# CPU.net
KiCad netlist of a schematic drawn in Altium Designer
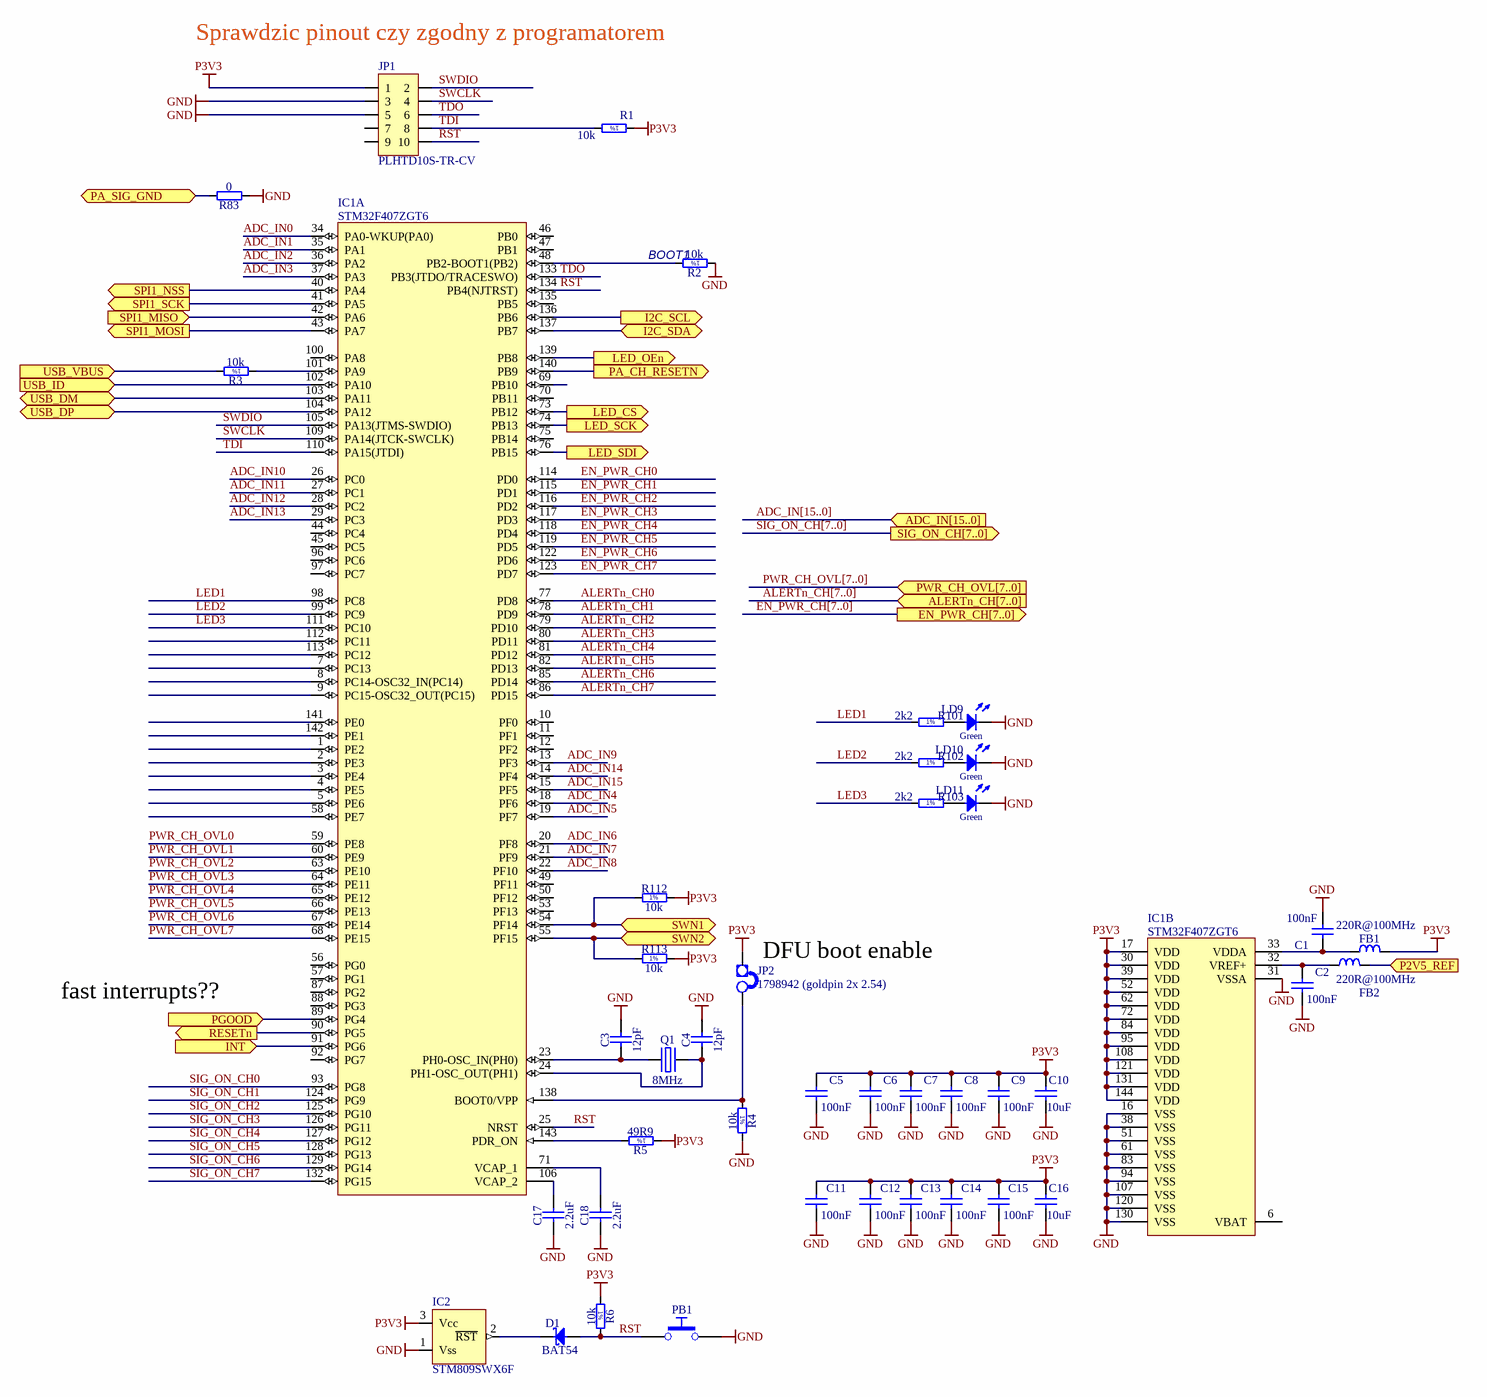
[diagram p0: CPU.SchDoc]

(export (version "E")
  (design (tool "Eeschema 10.0.6"))
  (components
    (comp (ref "C1")
      (value "100nF")
      (footprint "CAPC0603X33N")
      (description "Non-polarised capacitor")
      (fields
        (field (name "PART NUMBER") "CC0201_100NF_6.3V_10%_X5R")
        (field (name "VOLTAGE") "6.3V")
        (field (name "AUTHOR") "CERN DEM JLC")
      )
      (libsource (lib "Capacitors") (part "Capacitor - non polarized"))
    )
    (comp (ref "C2")
      (value "100nF")
      (footprint "CAPC0603X33N")
      (description "Non-polarised capacitor")
      (fields
        (field (name "PART NUMBER") "CC0201_100NF_6.3V_10%_X5R")
        (field (name "VOLTAGE") "6.3V")
        (field (name "AUTHOR") "CERN DEM JLC")
      )
      (libsource (lib "Capacitors") (part "Capacitor - non polarized"))
    )
    (comp (ref "C3")
      (value "12pF")
      (footprint "CAPC1005X55N")
      (description "Non-polarised capacitor")
      (fields
        (field (name "PART NUMBER") "CC0402_12PF_50V_5%_C0G")
        (field (name "VOLTAGE") "50V")
        (field (name "AUTHOR") "CERN DEM JLC")
      )
      (libsource (lib "Capacitors") (part "Capacitor - non polarized"))
    )
    (comp (ref "C4")
      (value "12pF")
      (footprint "CAPC1005X55N")
      (description "Non-polarised capacitor")
      (fields
        (field (name "PART NUMBER") "CC0402_12PF_50V_5%_C0G")
        (field (name "VOLTAGE") "50V")
        (field (name "AUTHOR") "CERN DEM JLC")
      )
      (libsource (lib "Capacitors") (part "Capacitor - non polarized"))
    )
    (comp (ref "C5")
      (value "100nF")
      (footprint "CAPC0603X33N")
      (description "Non-polarised capacitor")
      (fields
        (field (name "PART NUMBER") "CC0201_100NF_6.3V_10%_X5R")
        (field (name "VOLTAGE") "6.3V")
        (field (name "AUTHOR") "CERN DEM JLC")
      )
      (libsource (lib "Capacitors") (part "Capacitor - non polarized"))
    )
    (comp (ref "C6")
      (value "100nF")
      (footprint "CAPC0603X33N")
      (description "Non-polarised capacitor")
      (fields
        (field (name "PART NUMBER") "CC0201_100NF_6.3V_10%_X5R")
        (field (name "VOLTAGE") "6.3V")
        (field (name "AUTHOR") "CERN DEM JLC")
      )
      (libsource (lib "Capacitors") (part "Capacitor - non polarized"))
    )
    (comp (ref "C7")
      (value "100nF")
      (footprint "CAPC0603X33N")
      (description "Non-polarised capacitor")
      (fields
        (field (name "PART NUMBER") "CC0201_100NF_6.3V_10%_X5R")
        (field (name "VOLTAGE") "6.3V")
        (field (name "AUTHOR") "CERN DEM JLC")
      )
      (libsource (lib "Capacitors") (part "Capacitor - non polarized"))
    )
    (comp (ref "C8")
      (value "100nF")
      (footprint "CAPC0603X33N")
      (description "Non-polarised capacitor")
      (fields
        (field (name "PART NUMBER") "CC0201_100NF_6.3V_10%_X5R")
        (field (name "VOLTAGE") "6.3V")
        (field (name "AUTHOR") "CERN DEM JLC")
      )
      (libsource (lib "Capacitors") (part "Capacitor - non polarized"))
    )
    (comp (ref "C9")
      (value "100nF")
      (footprint "CAPC0603X33N")
      (description "Non-polarised capacitor")
      (fields
        (field (name "PART NUMBER") "CC0201_100NF_6.3V_10%_X5R")
        (field (name "VOLTAGE") "6.3V")
        (field (name "AUTHOR") "CERN DEM JLC")
      )
      (libsource (lib "Capacitors") (part "Capacitor - non polarized"))
    )
    (comp (ref "C10")
      (value "10uF")
      (footprint "CAPC2012X135N")
      (description "Non-polarised capacitor")
      (fields
        (field (name "PART NUMBER") "CC0805_10UF_10V_10%_X7R")
        (field (name "VOLTAGE") "10V")
        (field (name "AUTHOR") "CERN DEM JLC")
      )
      (libsource (lib "Capacitors") (part "Capacitor - non polarized"))
    )
    (comp (ref "C11")
      (value "100nF")
      (footprint "CAPC0603X33N")
      (description "Non-polarised capacitor")
      (fields
        (field (name "PART NUMBER") "CC0201_100NF_6.3V_10%_X5R")
        (field (name "VOLTAGE") "6.3V")
        (field (name "AUTHOR") "CERN DEM JLC")
      )
      (libsource (lib "Capacitors") (part "Capacitor - non polarized"))
    )
    (comp (ref "C12")
      (value "100nF")
      (footprint "CAPC0603X33N")
      (description "Non-polarised capacitor")
      (fields
        (field (name "PART NUMBER") "CC0201_100NF_6.3V_10%_X5R")
        (field (name "VOLTAGE") "6.3V")
        (field (name "AUTHOR") "CERN DEM JLC")
      )
      (libsource (lib "Capacitors") (part "Capacitor - non polarized"))
    )
    (comp (ref "C13")
      (value "100nF")
      (footprint "CAPC0603X33N")
      (description "Non-polarised capacitor")
      (fields
        (field (name "PART NUMBER") "CC0201_100NF_6.3V_10%_X5R")
        (field (name "VOLTAGE") "6.3V")
        (field (name "AUTHOR") "CERN DEM JLC")
      )
      (libsource (lib "Capacitors") (part "Capacitor - non polarized"))
    )
    (comp (ref "C14")
      (value "100nF")
      (footprint "CAPC0603X33N")
      (description "Non-polarised capacitor")
      (fields
        (field (name "PART NUMBER") "CC0201_100NF_6.3V_10%_X5R")
        (field (name "VOLTAGE") "6.3V")
        (field (name "AUTHOR") "CERN DEM JLC")
      )
      (libsource (lib "Capacitors") (part "Capacitor - non polarized"))
    )
    (comp (ref "C15")
      (value "100nF")
      (footprint "CAPC0603X33N")
      (description "Non-polarised capacitor")
      (fields
        (field (name "PART NUMBER") "CC0201_100NF_6.3V_10%_X5R")
        (field (name "VOLTAGE") "6.3V")
        (field (name "AUTHOR") "CERN DEM JLC")
      )
      (libsource (lib "Capacitors") (part "Capacitor - non polarized"))
    )
    (comp (ref "C16")
      (value "10uF")
      (footprint "CAPC2012X135N")
      (description "Non-polarised capacitor")
      (fields
        (field (name "PART NUMBER") "CC0805_10UF_10V_10%_X7R")
        (field (name "VOLTAGE") "10V")
        (field (name "AUTHOR") "CERN DEM JLC")
      )
      (libsource (lib "Capacitors") (part "Capacitor - non polarized"))
    )
    (comp (ref "C17")
      (value "2.2uF")
      (footprint "CAPC1608X90N")
      (description "Non-polarised capacitor")
      (fields
        (field (name "PART NUMBER") "CC0603_2.2UF_10V_20%_X7R")
        (field (name "VOLTAGE") "10V")
        (field (name "AUTHOR") "CERN DEM JLC")
      )
      (libsource (lib "Capacitors") (part "Capacitor - non polarized"))
    )
    (comp (ref "C18")
      (value "2.2uF")
      (footprint "CAPC1608X90N")
      (description "Non-polarised capacitor")
      (fields
        (field (name "PART NUMBER") "CC0603_2.2UF_10V_20%_X7R")
        (field (name "VOLTAGE") "10V")
        (field (name "AUTHOR") "CERN DEM JLC")
      )
      (libsource (lib "Capacitors") (part "Capacitor - non polarized"))
    )
    (comp (ref "D1")
      (value "BAT54")
      (footprint "SOT95P240X130-3N")
      (description "Diode Schottky  Anode Pin 1 Cathode Pin 3 (Pas de pin 2)")
      (fields
        (field (name "VOLTAGE") "30V")
        (field (name "POWER") "200mA")
        (field (name "AUTHOR") "CERN DEM JLC")
      )
      (libsource (lib "ICs And Semiconductors") (part "Diode Schottky A1C3"))
    )
    (comp (ref "FB1")
      (value "220R@100MHz")
      (footprint "INDC2012X105N")
      (description "Inductor")
      (fields
        (field (name "PART NUMBER") "IND0805_MURATA_BLM21PG221SN1D")
        (field (name "POWER") "2A")
        (field (name "AUTHOR") "CERN DEM JLC")
      )
      (libsource (lib "Inductors & Transformers") (part "Inductor"))
    )
    (comp (ref "FB2")
      (value "220R@100MHz")
      (footprint "INDC2012X105N")
      (description "Inductor")
      (fields
        (field (name "PART NUMBER") "IND0805_MURATA_BLM21PG221SN1D")
        (field (name "POWER") "2A")
        (field (name "AUTHOR") "CERN DEM JLC")
      )
      (libsource (lib "Inductors & Transformers") (part "Inductor"))
    )
    (comp (ref "IC1")
      (value "STM32F407ZGT6")
      (footprint "QFP50P2200X2200X160-144N")
      (fields (field (name "MANUFACTURER") "ST MICROELECTRONICS") (field (name "AUTHOR") "CERN DEM MR"))
      (libsource (lib "ICs And Semiconductors") (part "STM32F407ZGT6"))
    )
    (comp (ref "IC2")
      (value "STM809SWX6F")
      (footprint "SOT-23")
      (description "2.93V  Reset circuit")
      (libsource (lib "LIBRARY_SCH") (part "VMON_STM809"))
    )
    (comp (ref "JP1")
      (value "PLHTD10S-TR-CV")
      (footprint "PLHTD10S-TR-CV")
      (description "1.27 mm dual row goldpin (Maritex)")
      (libsource (lib "LIBRARY_SCH") (part "CON_2x5 1.27 SMT Male"))
    )
    (comp (ref "JP2")
      (value "1798942 (goldpin 2x 2.54)")
      (footprint "jump")
      (description "Jumper")
      (libsource (lib "LIBRARY_SCH") (part "JUMPER"))
    )
    (comp (ref "LD9")
      (value "Green")
      (footprint "LED_OSRAM_LGL29K")
      (description "LED Green 1C 2A")
      (fields
        (field (name "PART NUMBER") "LED_OSRAM_LG L29K-G2J1-24-Z")
        (field (name "MANUFACTURER") "OSRAM")
        (field (name "AUTHOR") "CERN DEM JLC")
      )
      (libsource (lib "ICs And Semiconductors") (part "LED Green 1C 2A"))
    )
    (comp (ref "LD10")
      (value "Green")
      (footprint "LED_OSRAM_LGL29K")
      (description "LED Green 1C 2A")
      (fields
        (field (name "PART NUMBER") "LED_OSRAM_LG L29K-G2J1-24-Z")
        (field (name "MANUFACTURER") "OSRAM")
        (field (name "AUTHOR") "CERN DEM JLC")
      )
      (libsource (lib "ICs And Semiconductors") (part "LED Green 1C 2A"))
    )
    (comp (ref "LD11")
      (value "Green")
      (footprint "LED_OSRAM_LGL29K")
      (description "LED Green 1C 2A")
      (fields
        (field (name "PART NUMBER") "LED_OSRAM_LG L29K-G2J1-24-Z")
        (field (name "MANUFACTURER") "OSRAM")
        (field (name "AUTHOR") "CERN DEM JLC")
      )
      (libsource (lib "ICs And Semiconductors") (part "LED Green 1C 2A"))
    )
    (comp (ref "PB1")
      (value "Push Button")
      (footprint "PB_TYCO_FSMSM")
      (description "Push-Button Switch SPDT")
      (fields
        (field (name "PART NUMBER") "PB_TYCO_FSMSM")
        (field (name "MANUFACTURER") "TYCO ELECTRONICS")
        (field (name "AUTHOR") "CERN DEM JLC")
      )
      (libsource (lib "Eletro-mechanical") (part "PB SPST 1NO-2NO"))
    )
    (comp (ref "Q1")
      (value "8MHz")
      (footprint "XTAL_TXC_7A")
      (description "Quartz Crystal")
      (fields
        (field (name "PART NUMBER") "XTAL_8MHZ_TXC_7A-8.000MAAE-T")
        (field (name "MANUFACTURER") "TXC CORPORATION")
        (field (name "AUTHOR") "CERN DEM JLC")
      )
      (libsource (lib "ICs And Semiconductors") (part "Quartz Crystal"))
    )
    (comp (ref "R1")
      (value "10k")
      (footprint "RESC1005X40N")
      (description "Resistor - 1%")
      (fields
        (field (name "PART NUMBER") "R0402_10K_1%_0.0625W_100PPM")
        (field (name "POWER") "0.0625W")
        (field (name "AUTHOR") "CERN DEM JLC")
      )
      (libsource (lib "Resistors") (part "Resistor - 1%"))
    )
    (comp (ref "R2")
      (value "10k")
      (footprint "RESC1005X40N")
      (description "Resistor - 1%")
      (fields
        (field (name "PART NUMBER") "R0402_10K_1%_0.0625W_100PPM")
        (field (name "POWER") "0.0625W")
        (field (name "AUTHOR") "CERN DEM JLC")
      )
      (libsource (lib "Resistors") (part "Resistor - 1%"))
    )
    (comp (ref "R3")
      (value "10k")
      (footprint "RESC1005X40N")
      (description "Resistor - 1%")
      (fields
        (field (name "PART NUMBER") "R0402_10K_1%_0.0625W_100PPM")
        (field (name "POWER") "0.0625W")
        (field (name "AUTHOR") "CERN DEM JLC")
      )
      (libsource (lib "Resistors") (part "Resistor - 1%"))
    )
    (comp (ref "R4")
      (value "10k")
      (footprint "RESC1005X40N")
      (description "Resistor - 1%")
      (fields
        (field (name "PART NUMBER") "R0402_10K_1%_0.0625W_100PPM")
        (field (name "POWER") "0.0625W")
        (field (name "AUTHOR") "CERN DEM JLC")
      )
      (libsource (lib "Resistors") (part "Resistor - 1%"))
    )
    (comp (ref "R5")
      (value "49R9")
      (footprint "RESC1005X40N")
      (description "Resistor - 1%")
      (fields
        (field (name "PART NUMBER") "R0402_49R9_1%_0.0625W_100PPM")
        (field (name "POWER") "0.0625W")
        (field (name "AUTHOR") "CERN DEM JLC")
      )
      (libsource (lib "Resistors") (part "Resistor - 1%"))
    )
    (comp (ref "R6")
      (value "10k")
      (footprint "RESC1005X40N")
      (description "Resistor - 1%")
      (fields
        (field (name "PART NUMBER") "R0402_10K_1%_0.0625W_100PPM")
        (field (name "POWER") "0.0625W")
        (field (name "AUTHOR") "CERN DEM JLC")
      )
      (libsource (lib "Resistors") (part "Resistor - 1%"))
    )
    (comp (ref "R83")
      (value "0")
      (footprint "RESC1005X40N")
      (description "Resistor")
      (fields
        (field (name "PART NUMBER") "R0402_0R_JUMPER")
        (field (name "MANUFACTURER") "GENERIC")
        (field (name "AUTHOR") "CERN DEM JLC")
      )
      (libsource (lib "Resistors") (part "Resistor"))
    )
    (comp (ref "R101")
      (value "2k2")
      (footprint "RESC1005X40N")
      (description "Resistor - 1%")
      (fields
        (field (name "PART NUMBER") "R0402_2K2_1%_0.0625W_100PPM")
        (field (name "POWER") "0.0625W")
        (field (name "AUTHOR") "CERN DEM JLC")
      )
      (libsource (lib "Resistors") (part "Resistor - 1%"))
    )
    (comp (ref "R102")
      (value "2k2")
      (footprint "RESC1005X40N")
      (description "Resistor - 1%")
      (fields
        (field (name "PART NUMBER") "R0402_2K2_1%_0.0625W_100PPM")
        (field (name "POWER") "0.0625W")
        (field (name "AUTHOR") "CERN DEM JLC")
      )
      (libsource (lib "Resistors") (part "Resistor - 1%"))
    )
    (comp (ref "R103")
      (value "2k2")
      (footprint "RESC1005X40N")
      (description "Resistor - 1%")
      (fields
        (field (name "PART NUMBER") "R0402_2K2_1%_0.0625W_100PPM")
        (field (name "POWER") "0.0625W")
        (field (name "AUTHOR") "CERN DEM JLC")
      )
      (libsource (lib "Resistors") (part "Resistor - 1%"))
    )
    (comp (ref "R112")
      (value "10k")
      (footprint "RESC1005X40N")
      (description "Resistor - 1%")
      (fields
        (field (name "PART NUMBER") "R0402_10K_1%_0.0625W_100PPM")
        (field (name "POWER") "0.0625W")
        (field (name "AUTHOR") "CERN DEM JLC")
      )
      (libsource (lib "Resistors") (part "Resistor - 1%"))
    )
    (comp (ref "R113")
      (value "10k")
      (footprint "RESC1005X40N")
      (description "Resistor - 1%")
      (fields
        (field (name "PART NUMBER") "R0402_10K_1%_0.0625W_100PPM")
        (field (name "POWER") "0.0625W")
        (field (name "AUTHOR") "CERN DEM JLC")
      )
      (libsource (lib "Resistors") (part "Resistor - 1%"))
    )
  )
  (nets
    (net (code "1") (name "/ADC_IN0") (class "Default")
      (node (ref "IC1") (pin "34") (pinfunction "PA0-WKUP(PA0)_34") (pintype "bidirectional"))
    )
    (net (code "2") (name "/ADC_IN1") (class "Default")
      (node (ref "IC1") (pin "35") (pinfunction "PA1_35") (pintype "bidirectional"))
    )
    (net (code "3") (name "/ADC_IN2") (class "Default")
      (node (ref "IC1") (pin "36") (pinfunction "PA2_36") (pintype "bidirectional"))
    )
    (net (code "4") (name "/ADC_IN3") (class "Default")
      (node (ref "IC1") (pin "37") (pinfunction "PA3_37") (pintype "bidirectional"))
    )
    (net (code "5") (name "/ADC_IN4") (class "Default")
      (node (ref "IC1") (pin "18") (pinfunction "PF6_18") (pintype "bidirectional"))
    )
    (net (code "6") (name "/ADC_IN5") (class "Default")
      (node (ref "IC1") (pin "19") (pinfunction "PF7_19") (pintype "bidirectional"))
    )
    (net (code "7") (name "/ADC_IN6") (class "Default")
      (node (ref "IC1") (pin "20") (pinfunction "PF8_20") (pintype "bidirectional"))
    )
    (net (code "8") (name "/ADC_IN7") (class "Default")
      (node (ref "IC1") (pin "21") (pinfunction "PF9_21") (pintype "bidirectional"))
    )
    (net (code "9") (name "/ADC_IN8") (class "Default")
      (node (ref "IC1") (pin "22") (pinfunction "PF10_22") (pintype "bidirectional"))
    )
    (net (code "10") (name "/ADC_IN9") (class "Default")
      (node (ref "IC1") (pin "13") (pinfunction "PF3_13") (pintype "bidirectional"))
    )
    (net (code "11") (name "/ADC_IN10") (class "Default")
      (node (ref "IC1") (pin "26") (pinfunction "PC0_26") (pintype "bidirectional"))
    )
    (net (code "12") (name "/ADC_IN11") (class "Default")
      (node (ref "IC1") (pin "27") (pinfunction "PC1_27") (pintype "bidirectional"))
    )
    (net (code "13") (name "/ADC_IN12") (class "Default")
      (node (ref "IC1") (pin "28") (pinfunction "PC2_28") (pintype "bidirectional"))
    )
    (net (code "14") (name "/ADC_IN13") (class "Default")
      (node (ref "IC1") (pin "29") (pinfunction "PC3_29") (pintype "bidirectional"))
    )
    (net (code "15") (name "/ADC_IN14") (class "Default")
      (node (ref "IC1") (pin "14") (pinfunction "PF4_14") (pintype "bidirectional"))
    )
    (net (code "16") (name "/ADC_IN15") (class "Default")
      (node (ref "IC1") (pin "15") (pinfunction "PF5_15") (pintype "bidirectional"))
    )
    (net (code "18") (name "/ALERTn_CH0") (class "Default")
      (node (ref "IC1") (pin "77") (pinfunction "PD8_77") (pintype "bidirectional"))
    )
    (net (code "19") (name "/ALERTn_CH1") (class "Default")
      (node (ref "IC1") (pin "78") (pinfunction "PD9_78") (pintype "bidirectional"))
    )
    (net (code "20") (name "/ALERTn_CH2") (class "Default")
      (node (ref "IC1") (pin "79") (pinfunction "PD10_79") (pintype "bidirectional"))
    )
    (net (code "21") (name "/ALERTn_CH3") (class "Default")
      (node (ref "IC1") (pin "80") (pinfunction "PD11_80") (pintype "bidirectional"))
    )
    (net (code "22") (name "/ALERTn_CH4") (class "Default")
      (node (ref "IC1") (pin "81") (pinfunction "PD12_81") (pintype "bidirectional"))
    )
    (net (code "23") (name "/ALERTn_CH5") (class "Default")
      (node (ref "IC1") (pin "82") (pinfunction "PD13_82") (pintype "bidirectional"))
    )
    (net (code "24") (name "/ALERTn_CH6") (class "Default")
      (node (ref "IC1") (pin "85") (pinfunction "PD14_85") (pintype "bidirectional"))
    )
    (net (code "25") (name "/ALERTn_CH7") (class "Default")
      (node (ref "IC1") (pin "86") (pinfunction "PD15_86") (pintype "bidirectional"))
    )
    (net (code "27") (name "/EN_PWR_CH0") (class "Default")
      (node (ref "IC1") (pin "114") (pinfunction "PD0_114") (pintype "bidirectional"))
    )
    (net (code "28") (name "/EN_PWR_CH1") (class "Default")
      (node (ref "IC1") (pin "115") (pinfunction "PD1_115") (pintype "bidirectional"))
    )
    (net (code "29") (name "/EN_PWR_CH2") (class "Default")
      (node (ref "IC1") (pin "116") (pinfunction "PD2_116") (pintype "bidirectional"))
    )
    (net (code "30") (name "/EN_PWR_CH3") (class "Default")
      (node (ref "IC1") (pin "117") (pinfunction "PD3_117") (pintype "bidirectional"))
    )
    (net (code "31") (name "/EN_PWR_CH4") (class "Default")
      (node (ref "IC1") (pin "118") (pinfunction "PD4_118") (pintype "bidirectional"))
    )
    (net (code "32") (name "/EN_PWR_CH5") (class "Default")
      (node (ref "IC1") (pin "119") (pinfunction "PD5_119") (pintype "bidirectional"))
    )
    (net (code "33") (name "/EN_PWR_CH6") (class "Default")
      (node (ref "IC1") (pin "122") (pinfunction "PD6_122") (pintype "bidirectional"))
    )
    (net (code "34") (name "/EN_PWR_CH7") (class "Default")
      (node (ref "IC1") (pin "123") (pinfunction "PD7_123") (pintype "bidirectional"))
    )
    (net (code "36") (name "/I2C_SCL") (class "Default")
      (node (ref "IC1") (pin "136") (pinfunction "PB6_136") (pintype "bidirectional"))
    )
    (net (code "37") (name "/I2C_SDA") (class "Default")
      (node (ref "IC1") (pin "137") (pinfunction "PB7_137") (pintype "bidirectional"))
    )
    (net (code "38") (name "/INT") (class "Default")
      (node (ref "IC1") (pin "91") (pinfunction "PG6_91") (pintype "bidirectional"))
    )
    (net (code "39") (name "/LED1") (class "Default")
      (node (ref "IC1") (pin "98") (pinfunction "PC8_98") (pintype "bidirectional"))
      (node (ref "R101") (pin "1") (pinfunction "1_1") (pintype "passive"))
    )
    (net (code "40") (name "/LED2") (class "Default")
      (node (ref "IC1") (pin "99") (pinfunction "PC9_99") (pintype "bidirectional"))
      (node (ref "R102") (pin "1") (pinfunction "1_1") (pintype "passive"))
    )
    (net (code "41") (name "/LED3") (class "Default")
      (node (ref "IC1") (pin "111") (pinfunction "PC10_111") (pintype "bidirectional"))
      (node (ref "R103") (pin "1") (pinfunction "1_1") (pintype "passive"))
    )
    (net (code "42") (name "/LED_CS") (class "Default")
      (node (ref "IC1") (pin "73") (pinfunction "PB12_73") (pintype "bidirectional"))
    )
    (net (code "43") (name "/LED_OEn") (class "Default")
      (node (ref "IC1") (pin "139") (pinfunction "PB8_139") (pintype "bidirectional"))
    )
    (net (code "44") (name "/LED_SCK") (class "Default")
      (node (ref "IC1") (pin "74") (pinfunction "PB13_74") (pintype "bidirectional"))
    )
    (net (code "45") (name "/LED_SDI") (class "Default")
      (node (ref "IC1") (pin "76") (pinfunction "PB15_76") (pintype "bidirectional"))
    )
    (net (code "46") (name "/P2V5_REF") (class "Default")
      (node (ref "FB2") (pin "2") (pinfunction "2_2") (pintype "passive"))
    )
    (net (code "47") (name "/PA_CH_RESETN") (class "Default")
      (node (ref "IC1") (pin "140") (pinfunction "PB9_140") (pintype "bidirectional"))
    )
    (net (code "48") (name "/PA_SIG_GND") (class "Default")
      (node (ref "R83") (pin "2") (pinfunction "2_2") (pintype "passive"))
    )
    (net (code "49") (name "/PGOOD") (class "Default")
      (node (ref "IC1") (pin "89") (pinfunction "PG4_89") (pintype "bidirectional"))
    )
    (net (code "50") (name "/PWR_CH_OVL0") (class "Default")
      (node (ref "IC1") (pin "59") (pinfunction "PE8_59") (pintype "bidirectional"))
    )
    (net (code "51") (name "/PWR_CH_OVL1") (class "Default")
      (node (ref "IC1") (pin "60") (pinfunction "PE9_60") (pintype "bidirectional"))
    )
    (net (code "52") (name "/PWR_CH_OVL2") (class "Default")
      (node (ref "IC1") (pin "63") (pinfunction "PE10_63") (pintype "bidirectional"))
    )
    (net (code "53") (name "/PWR_CH_OVL3") (class "Default")
      (node (ref "IC1") (pin "64") (pinfunction "PE11_64") (pintype "bidirectional"))
    )
    (net (code "54") (name "/PWR_CH_OVL4") (class "Default")
      (node (ref "IC1") (pin "65") (pinfunction "PE12_65") (pintype "bidirectional"))
    )
    (net (code "55") (name "/PWR_CH_OVL5") (class "Default")
      (node (ref "IC1") (pin "66") (pinfunction "PE13_66") (pintype "bidirectional"))
    )
    (net (code "56") (name "/PWR_CH_OVL6") (class "Default")
      (node (ref "IC1") (pin "67") (pinfunction "PE14_67") (pintype "bidirectional"))
    )
    (net (code "57") (name "/PWR_CH_OVL7") (class "Default")
      (node (ref "IC1") (pin "68") (pinfunction "PE15_68") (pintype "bidirectional"))
    )
    (net (code "59") (name "/RESETn") (class "Default")
      (node (ref "IC1") (pin "90") (pinfunction "PG5_90") (pintype "bidirectional"))
    )
    (net (code "60") (name "/RST") (class "Default")
      (node (ref "D1") (pin "1") (pinfunction "A_1") (pintype "passive"))
      (node (ref "IC1") (pin "134") (pinfunction "PB4(NJTRST)_134") (pintype "bidirectional"))
      (node (ref "IC1") (pin "25") (pinfunction "NRST_25") (pintype "bidirectional"))
      (node (ref "JP1") (pin "10") (pinfunction "10_10") (pintype "passive"))
      (node (ref "PB1") (pin "1") (pinfunction "1_1") (pintype "passive"))
      (node (ref "R6") (pin "2") (pinfunction "2_2") (pintype "passive"))
    )
    (net (code "61") (name "/SIG_ON_CH0") (class "Default")
      (node (ref "IC1") (pin "93") (pinfunction "PG8_93") (pintype "bidirectional"))
    )
    (net (code "62") (name "/SIG_ON_CH1") (class "Default")
      (node (ref "IC1") (pin "124") (pinfunction "PG9_124") (pintype "bidirectional"))
    )
    (net (code "63") (name "/SIG_ON_CH2") (class "Default")
      (node (ref "IC1") (pin "125") (pinfunction "PG10_125") (pintype "bidirectional"))
    )
    (net (code "64") (name "/SIG_ON_CH3") (class "Default")
      (node (ref "IC1") (pin "126") (pinfunction "PG11_126") (pintype "bidirectional"))
    )
    (net (code "65") (name "/SIG_ON_CH4") (class "Default")
      (node (ref "IC1") (pin "127") (pinfunction "PG12_127") (pintype "bidirectional"))
    )
    (net (code "66") (name "/SIG_ON_CH5") (class "Default")
      (node (ref "IC1") (pin "128") (pinfunction "PG13_128") (pintype "bidirectional"))
    )
    (net (code "67") (name "/SIG_ON_CH6") (class "Default")
      (node (ref "IC1") (pin "129") (pinfunction "PG14_129") (pintype "bidirectional"))
    )
    (net (code "68") (name "/SIG_ON_CH7") (class "Default")
      (node (ref "IC1") (pin "132") (pinfunction "PG15_132") (pintype "bidirectional"))
    )
    (net (code "70") (name "/SPI1_MISO") (class "Default")
      (node (ref "IC1") (pin "42") (pinfunction "PA6_42") (pintype "bidirectional"))
    )
    (net (code "71") (name "/SPI1_MOSI") (class "Default")
      (node (ref "IC1") (pin "43") (pinfunction "PA7_43") (pintype "bidirectional"))
    )
    (net (code "72") (name "/SPI1_NSS") (class "Default")
      (node (ref "IC1") (pin "40") (pinfunction "PA4_40") (pintype "bidirectional"))
    )
    (net (code "73") (name "/SPI1_SCK") (class "Default")
      (node (ref "IC1") (pin "41") (pinfunction "PA5_41") (pintype "bidirectional"))
    )
    (net (code "74") (name "/SWCLK") (class "Default")
      (node (ref "IC1") (pin "109") (pinfunction "PA14(JTCK-SWCLK)_109") (pintype "bidirectional"))
      (node (ref "JP1") (pin "4") (pinfunction "4_4") (pintype "passive"))
    )
    (net (code "75") (name "/SWDIO") (class "Default")
      (node (ref "IC1") (pin "105") (pinfunction "PA13(JTMS-SWDIO)_105") (pintype "bidirectional"))
      (node (ref "JP1") (pin "2") (pinfunction "2_2") (pintype "passive"))
    )
    (net (code "76") (name "/SWN1") (class "Default")
      (node (ref "IC1") (pin "54") (pinfunction "PF14_54") (pintype "bidirectional"))
      (node (ref "R112") (pin "1") (pinfunction "1_1") (pintype "passive"))
    )
    (net (code "77") (name "/SWN2") (class "Default")
      (node (ref "IC1") (pin "55") (pinfunction "PF15_55") (pintype "bidirectional"))
      (node (ref "R113") (pin "1") (pinfunction "1_1") (pintype "passive"))
    )
    (net (code "78") (name "/TDI") (class "Default")
      (node (ref "IC1") (pin "110") (pinfunction "PA15(JTDI)_110") (pintype "bidirectional"))
      (node (ref "JP1") (pin "8") (pinfunction "8_8") (pintype "passive"))
      (node (ref "R1") (pin "2") (pinfunction "2_2") (pintype "passive"))
    )
    (net (code "79") (name "/TDO") (class "Default")
      (node (ref "IC1") (pin "133") (pinfunction "PB3(JTDO/TRACESWO)_133") (pintype "bidirectional"))
      (node (ref "JP1") (pin "6") (pinfunction "6_6") (pintype "passive"))
    )
    (net (code "80") (name "/USB_DM") (class "Default")
      (node (ref "IC1") (pin "103") (pinfunction "PA11_103") (pintype "bidirectional"))
    )
    (net (code "81") (name "/USB_DP") (class "Default")
      (node (ref "IC1") (pin "104") (pinfunction "PA12_104") (pintype "bidirectional"))
    )
    (net (code "82") (name "/USB_ID") (class "Default")
      (node (ref "IC1") (pin "102") (pinfunction "PA10_102") (pintype "bidirectional"))
    )
    (net (code "83") (name "/USB_VBUS") (class "Default")
      (node (ref "R3") (pin "2") (pinfunction "2_2") (pintype "passive"))
    )
    (net (code "84") (name "GND") (class "Default")
      (node (ref "C1") (pin "2") (pinfunction "2_2") (pintype "passive"))
      (node (ref "C10") (pin "2") (pinfunction "2_2") (pintype "passive"))
      (node (ref "C11") (pin "2") (pinfunction "2_2") (pintype "passive"))
      (node (ref "C12") (pin "2") (pinfunction "2_2") (pintype "passive"))
      (node (ref "C13") (pin "2") (pinfunction "2_2") (pintype "passive"))
      (node (ref "C14") (pin "2") (pinfunction "2_2") (pintype "passive"))
      (node (ref "C15") (pin "2") (pinfunction "2_2") (pintype "passive"))
      (node (ref "C16") (pin "2") (pinfunction "2_2") (pintype "passive"))
      (node (ref "C17") (pin "1") (pinfunction "1_1") (pintype "passive"))
      (node (ref "C18") (pin "1") (pinfunction "1_1") (pintype "passive"))
      (node (ref "C2") (pin "2") (pinfunction "2_2") (pintype "passive"))
      (node (ref "C3") (pin "2") (pinfunction "2_2") (pintype "passive"))
      (node (ref "C4") (pin "2") (pinfunction "2_2") (pintype "passive"))
      (node (ref "C5") (pin "2") (pinfunction "2_2") (pintype "passive"))
      (node (ref "C6") (pin "2") (pinfunction "2_2") (pintype "passive"))
      (node (ref "C7") (pin "2") (pinfunction "2_2") (pintype "passive"))
      (node (ref "C8") (pin "2") (pinfunction "2_2") (pintype "passive"))
      (node (ref "C9") (pin "2") (pinfunction "2_2") (pintype "passive"))
      (node (ref "IC1") (pin "107") (pinfunction "VSS_107") (pintype "power_in"))
      (node (ref "IC1") (pin "120") (pinfunction "VSS_120") (pintype "power_in"))
      (node (ref "IC1") (pin "130") (pinfunction "VSS_130") (pintype "power_in"))
      (node (ref "IC1") (pin "16") (pinfunction "VSS_16") (pintype "power_in"))
      (node (ref "IC1") (pin "31") (pinfunction "VSSA_31") (pintype "power_in"))
      (node (ref "IC1") (pin "38") (pinfunction "VSS_38") (pintype "power_in"))
      (node (ref "IC1") (pin "51") (pinfunction "VSS_51") (pintype "power_in"))
      (node (ref "IC1") (pin "61") (pinfunction "VSS_61") (pintype "power_in"))
      (node (ref "IC1") (pin "83") (pinfunction "VSS_83") (pintype "power_in"))
      (node (ref "IC1") (pin "94") (pinfunction "VSS_94") (pintype "power_in"))
      (node (ref "IC2") (pin "1") (pinfunction "Vss_1") (pintype "power_in"))
      (node (ref "JP1") (pin "3") (pinfunction "3_3") (pintype "passive"))
      (node (ref "JP1") (pin "5") (pinfunction "5_5") (pintype "passive"))
      (node (ref "LD10") (pin "1") (pinfunction "C_1") (pintype "passive"))
      (node (ref "LD11") (pin "1") (pinfunction "C_1") (pintype "passive"))
      (node (ref "LD9") (pin "1") (pinfunction "C_1") (pintype "passive"))
      (node (ref "PB1") (pin "2") (pinfunction "2_2") (pintype "passive"))
      (node (ref "R2") (pin "1") (pinfunction "1_1") (pintype "passive"))
      (node (ref "R4") (pin "2") (pinfunction "2_2") (pintype "passive"))
      (node (ref "R83") (pin "1") (pinfunction "1_1") (pintype "passive"))
    )
    (net (code "85") (name "Net-(D1-C)") (class "Default")
      (node (ref "D1") (pin "3") (pinfunction "C_3") (pintype "passive"))
      (node (ref "IC2") (pin "2") (pinfunction "~{RST}_2") (pintype "output"))
    )
    (net (code "86") (name "Net-(IC1A-BOOT0{slash}VPP)") (class "Default")
      (node (ref "IC1") (pin "138") (pinfunction "BOOT0/VPP_138") (pintype "input"))
      (node (ref "JP2") (pin "2") (pinfunction "E2_2") (pintype "passive"))
      (node (ref "R4") (pin "1") (pinfunction "1_1") (pintype "passive"))
    )
    (net (code "87") (name "Net-(IC1A-PA9)") (class "Default")
      (node (ref "IC1") (pin "101") (pinfunction "PA9_101") (pintype "bidirectional"))
      (node (ref "R3") (pin "1") (pinfunction "1_1") (pintype "passive"))
    )
    (net (code "88") (name "Net-(IC1A-PB2-BOOT1(PB2))") (class "Default")
      (node (ref "IC1") (pin "48") (pinfunction "PB2-BOOT1(PB2)_48") (pintype "bidirectional"))
      (node (ref "R2") (pin "2") (pinfunction "2_2") (pintype "passive"))
    )
    (net (code "89") (name "Net-(IC1A-PDR_ON)") (class "Default")
      (node (ref "IC1") (pin "143") (pinfunction "PDR_ON_143") (pintype "input"))
      (node (ref "R5") (pin "2") (pinfunction "2_2") (pintype "passive"))
    )
    (net (code "90") (name "Net-(IC1A-PH0-OSC_IN(PH0))") (class "Default")
      (node (ref "C3") (pin "1") (pinfunction "1_1") (pintype "passive"))
      (node (ref "IC1") (pin "23") (pinfunction "PH0-OSC_IN(PH0)_23") (pintype "bidirectional"))
      (node (ref "Q1") (pin "1") (pinfunction "OSC1_1") (pintype "passive"))
    )
    (net (code "91") (name "Net-(IC1A-PH1-OSC_OUT(PH1))") (class "Default")
      (node (ref "C4") (pin "1") (pinfunction "1_1") (pintype "passive"))
      (node (ref "IC1") (pin "24") (pinfunction "PH1-OSC_OUT(PH1)_24") (pintype "bidirectional"))
      (node (ref "Q1") (pin "2") (pinfunction "OSC2_2") (pintype "passive"))
    )
    (net (code "92") (name "Net-(IC1A-VCAP_1)") (class "Default")
      (node (ref "C18") (pin "2") (pinfunction "2_2") (pintype "passive"))
      (node (ref "IC1") (pin "71") (pinfunction "VCAP_1_71") (pintype "power_in"))
    )
    (net (code "93") (name "Net-(IC1A-VCAP_2)") (class "Default")
      (node (ref "C17") (pin "2") (pinfunction "2_2") (pintype "passive"))
      (node (ref "IC1") (pin "106") (pinfunction "VCAP_2_106") (pintype "power_in"))
    )
    (net (code "94") (name "Net-(IC1B-VDDA)") (class "Default")
      (node (ref "C1") (pin "1") (pinfunction "1_1") (pintype "passive"))
      (node (ref "FB1") (pin "1") (pinfunction "1_1") (pintype "passive"))
      (node (ref "IC1") (pin "33") (pinfunction "VDDA_33") (pintype "power_in"))
    )
    (net (code "95") (name "Net-(IC1B-VREF+)") (class "Default")
      (node (ref "C2") (pin "1") (pinfunction "1_1") (pintype "passive"))
      (node (ref "FB2") (pin "1") (pinfunction "1_1") (pintype "passive"))
      (node (ref "IC1") (pin "32") (pinfunction "VREF+_32") (pintype "power_in"))
    )
    (net (code "96") (name "Net-(LD9-A)") (class "Default")
      (node (ref "LD9") (pin "2") (pinfunction "A_2") (pintype "passive"))
      (node (ref "R101") (pin "2") (pinfunction "2_2") (pintype "passive"))
    )
    (net (code "97") (name "Net-(LD10-A)") (class "Default")
      (node (ref "LD10") (pin "2") (pinfunction "A_2") (pintype "passive"))
      (node (ref "R102") (pin "2") (pinfunction "2_2") (pintype "passive"))
    )
    (net (code "98") (name "Net-(LD11-A)") (class "Default")
      (node (ref "LD11") (pin "2") (pinfunction "A_2") (pintype "passive"))
      (node (ref "R103") (pin "2") (pinfunction "2_2") (pintype "passive"))
    )
    (net (code "99") (name "P3V3") (class "Default")
      (node (ref "C10") (pin "1") (pinfunction "1_1") (pintype "passive"))
      (node (ref "C11") (pin "1") (pinfunction "1_1") (pintype "passive"))
      (node (ref "C12") (pin "1") (pinfunction "1_1") (pintype "passive"))
      (node (ref "C13") (pin "1") (pinfunction "1_1") (pintype "passive"))
      (node (ref "C14") (pin "1") (pinfunction "1_1") (pintype "passive"))
      (node (ref "C15") (pin "1") (pinfunction "1_1") (pintype "passive"))
      (node (ref "C16") (pin "1") (pinfunction "1_1") (pintype "passive"))
      (node (ref "C5") (pin "1") (pinfunction "1_1") (pintype "passive"))
      (node (ref "C6") (pin "1") (pinfunction "1_1") (pintype "passive"))
      (node (ref "C7") (pin "1") (pinfunction "1_1") (pintype "passive"))
      (node (ref "C8") (pin "1") (pinfunction "1_1") (pintype "passive"))
      (node (ref "C9") (pin "1") (pinfunction "1_1") (pintype "passive"))
      (node (ref "FB1") (pin "2") (pinfunction "2_2") (pintype "passive"))
      (node (ref "IC1") (pin "108") (pinfunction "VDD_108") (pintype "power_in"))
      (node (ref "IC1") (pin "121") (pinfunction "VDD_121") (pintype "power_in"))
      (node (ref "IC1") (pin "131") (pinfunction "VDD_131") (pintype "power_in"))
      (node (ref "IC1") (pin "144") (pinfunction "VDD_144") (pintype "power_in"))
      (node (ref "IC1") (pin "17") (pinfunction "VDD_17") (pintype "power_in"))
      (node (ref "IC1") (pin "30") (pinfunction "VDD_30") (pintype "power_in"))
      (node (ref "IC1") (pin "39") (pinfunction "VDD_39") (pintype "power_in"))
      (node (ref "IC1") (pin "52") (pinfunction "VDD_52") (pintype "power_in"))
      (node (ref "IC1") (pin "62") (pinfunction "VDD_62") (pintype "power_in"))
      (node (ref "IC1") (pin "72") (pinfunction "VDD_72") (pintype "power_in"))
      (node (ref "IC1") (pin "84") (pinfunction "VDD_84") (pintype "power_in"))
      (node (ref "IC1") (pin "95") (pinfunction "VDD_95") (pintype "power_in"))
      (node (ref "IC2") (pin "3") (pinfunction "Vcc_3") (pintype "power_in"))
      (node (ref "JP1") (pin "1") (pinfunction "1_1") (pintype "passive"))
      (node (ref "JP2") (pin "1") (pinfunction "E1_1") (pintype "passive"))
      (node (ref "R1") (pin "1") (pinfunction "1_1") (pintype "passive"))
      (node (ref "R112") (pin "2") (pinfunction "2_2") (pintype "passive"))
      (node (ref "R113") (pin "2") (pinfunction "2_2") (pintype "passive"))
      (node (ref "R5") (pin "1") (pinfunction "1_1") (pintype "passive"))
      (node (ref "R6") (pin "1") (pinfunction "1_1") (pintype "passive"))
    )
    (net (code "100") (name "unconnected-(IC1A-PA8-Pad100)") (class "Default")
      (node (ref "IC1") (pin "100") (pinfunction "PA8_100") (pintype "bidirectional"))
    )
    (net (code "101") (name "unconnected-(IC1A-PB0-Pad46)") (class "Default")
      (node (ref "IC1") (pin "46") (pinfunction "PB0_46") (pintype "bidirectional"))
    )
    (net (code "102") (name "unconnected-(IC1A-PB1-Pad47)") (class "Default")
      (node (ref "IC1") (pin "47") (pinfunction "PB1_47") (pintype "bidirectional"))
    )
    (net (code "103") (name "unconnected-(IC1A-PB5-Pad135)") (class "Default")
      (node (ref "IC1") (pin "135") (pinfunction "PB5_135") (pintype "bidirectional"))
    )
    (net (code "104") (name "unconnected-(IC1A-PB10-Pad69)") (class "Default")
      (node (ref "IC1") (pin "69") (pinfunction "PB10_69") (pintype "bidirectional"))
    )
    (net (code "105") (name "unconnected-(IC1A-PB11-Pad70)") (class "Default")
      (node (ref "IC1") (pin "70") (pinfunction "PB11_70") (pintype "bidirectional"))
    )
    (net (code "106") (name "unconnected-(IC1A-PB14-Pad75)") (class "Default")
      (node (ref "IC1") (pin "75") (pinfunction "PB14_75") (pintype "bidirectional"))
    )
    (net (code "107") (name "unconnected-(IC1A-PC4-Pad44)") (class "Default")
      (node (ref "IC1") (pin "44") (pinfunction "PC4_44") (pintype "bidirectional"))
    )
    (net (code "108") (name "unconnected-(IC1A-PC5-Pad45)") (class "Default")
      (node (ref "IC1") (pin "45") (pinfunction "PC5_45") (pintype "bidirectional"))
    )
    (net (code "109") (name "unconnected-(IC1A-PC6-Pad96)") (class "Default")
      (node (ref "IC1") (pin "96") (pinfunction "PC6_96") (pintype "bidirectional"))
    )
    (net (code "110") (name "unconnected-(IC1A-PC7-Pad97)") (class "Default")
      (node (ref "IC1") (pin "97") (pinfunction "PC7_97") (pintype "bidirectional"))
    )
    (net (code "111") (name "unconnected-(IC1A-PC11-Pad112)") (class "Default")
      (node (ref "IC1") (pin "112") (pinfunction "PC11_112") (pintype "bidirectional"))
    )
    (net (code "112") (name "unconnected-(IC1A-PC12-Pad113)") (class "Default")
      (node (ref "IC1") (pin "113") (pinfunction "PC12_113") (pintype "bidirectional"))
    )
    (net (code "113") (name "unconnected-(IC1A-PC13-Pad7)") (class "Default")
      (node (ref "IC1") (pin "7") (pinfunction "PC13_7") (pintype "bidirectional"))
    )
    (net (code "114") (name "unconnected-(IC1A-PC14-OSC32_IN(PC14)-Pad8)") (class "Default")
      (node (ref "IC1") (pin "8") (pinfunction "PC14-OSC32_IN(PC14)_8") (pintype "bidirectional"))
    )
    (net (code "115") (name "unconnected-(IC1A-PC15-OSC32_OUT(PC15)-Pad9)") (class "Default")
      (node (ref "IC1") (pin "9") (pinfunction "PC15-OSC32_OUT(PC15)_9") (pintype "bidirectional"))
    )
    (net (code "116") (name "unconnected-(IC1A-PE0-Pad141)") (class "Default")
      (node (ref "IC1") (pin "141") (pinfunction "PE0_141") (pintype "bidirectional"))
    )
    (net (code "117") (name "unconnected-(IC1A-PE1-Pad142)") (class "Default")
      (node (ref "IC1") (pin "142") (pinfunction "PE1_142") (pintype "bidirectional"))
    )
    (net (code "118") (name "unconnected-(IC1A-PE2-Pad1)") (class "Default")
      (node (ref "IC1") (pin "1") (pinfunction "PE2_1") (pintype "bidirectional"))
    )
    (net (code "119") (name "unconnected-(IC1A-PE3-Pad2)") (class "Default")
      (node (ref "IC1") (pin "2") (pinfunction "PE3_2") (pintype "bidirectional"))
    )
    (net (code "120") (name "unconnected-(IC1A-PE4-Pad3)") (class "Default")
      (node (ref "IC1") (pin "3") (pinfunction "PE4_3") (pintype "bidirectional"))
    )
    (net (code "121") (name "unconnected-(IC1A-PE5-Pad4)") (class "Default")
      (node (ref "IC1") (pin "4") (pinfunction "PE5_4") (pintype "bidirectional"))
    )
    (net (code "122") (name "unconnected-(IC1A-PE6-Pad5)") (class "Default")
      (node (ref "IC1") (pin "5") (pinfunction "PE6_5") (pintype "bidirectional"))
    )
    (net (code "123") (name "unconnected-(IC1A-PE7-Pad58)") (class "Default")
      (node (ref "IC1") (pin "58") (pinfunction "PE7_58") (pintype "bidirectional"))
    )
    (net (code "124") (name "unconnected-(IC1A-PF0-Pad10)") (class "Default")
      (node (ref "IC1") (pin "10") (pinfunction "PF0_10") (pintype "bidirectional"))
    )
    (net (code "125") (name "unconnected-(IC1A-PF1-Pad11)") (class "Default")
      (node (ref "IC1") (pin "11") (pinfunction "PF1_11") (pintype "bidirectional"))
    )
    (net (code "126") (name "unconnected-(IC1A-PF2-Pad12)") (class "Default")
      (node (ref "IC1") (pin "12") (pinfunction "PF2_12") (pintype "bidirectional"))
    )
    (net (code "127") (name "unconnected-(IC1A-PF11-Pad49)") (class "Default")
      (node (ref "IC1") (pin "49") (pinfunction "PF11_49") (pintype "bidirectional"))
    )
    (net (code "128") (name "unconnected-(IC1A-PF12-Pad50)") (class "Default")
      (node (ref "IC1") (pin "50") (pinfunction "PF12_50") (pintype "bidirectional"))
    )
    (net (code "129") (name "unconnected-(IC1A-PF13-Pad53)") (class "Default")
      (node (ref "IC1") (pin "53") (pinfunction "PF13_53") (pintype "bidirectional"))
    )
    (net (code "130") (name "unconnected-(IC1A-PG0-Pad56)") (class "Default")
      (node (ref "IC1") (pin "56") (pinfunction "PG0_56") (pintype "bidirectional"))
    )
    (net (code "131") (name "unconnected-(IC1A-PG1-Pad57)") (class "Default")
      (node (ref "IC1") (pin "57") (pinfunction "PG1_57") (pintype "bidirectional"))
    )
    (net (code "132") (name "unconnected-(IC1A-PG2-Pad87)") (class "Default")
      (node (ref "IC1") (pin "87") (pinfunction "PG2_87") (pintype "bidirectional"))
    )
    (net (code "133") (name "unconnected-(IC1A-PG3-Pad88)") (class "Default")
      (node (ref "IC1") (pin "88") (pinfunction "PG3_88") (pintype "bidirectional"))
    )
    (net (code "134") (name "unconnected-(IC1A-PG7-Pad92)") (class "Default")
      (node (ref "IC1") (pin "92") (pinfunction "PG7_92") (pintype "bidirectional"))
    )
    (net (code "135") (name "unconnected-(IC1B-VBAT-Pad6)") (class "Default")
      (node (ref "IC1") (pin "6") (pinfunction "VBAT_6") (pintype "power_in"))
    )
    (net (code "136") (name "unconnected-(JP1-Pad7)") (class "Default")
      (node (ref "JP1") (pin "7") (pinfunction "7_7") (pintype "passive"))
    )
    (net (code "137") (name "unconnected-(JP1-Pad9)") (class "Default")
      (node (ref "JP1") (pin "9") (pinfunction "9_9") (pintype "passive"))
    )
  )
)
